# Sec_Controller_Sheet3.net
KiCad netlist of a schematic drawn in Altium Designer
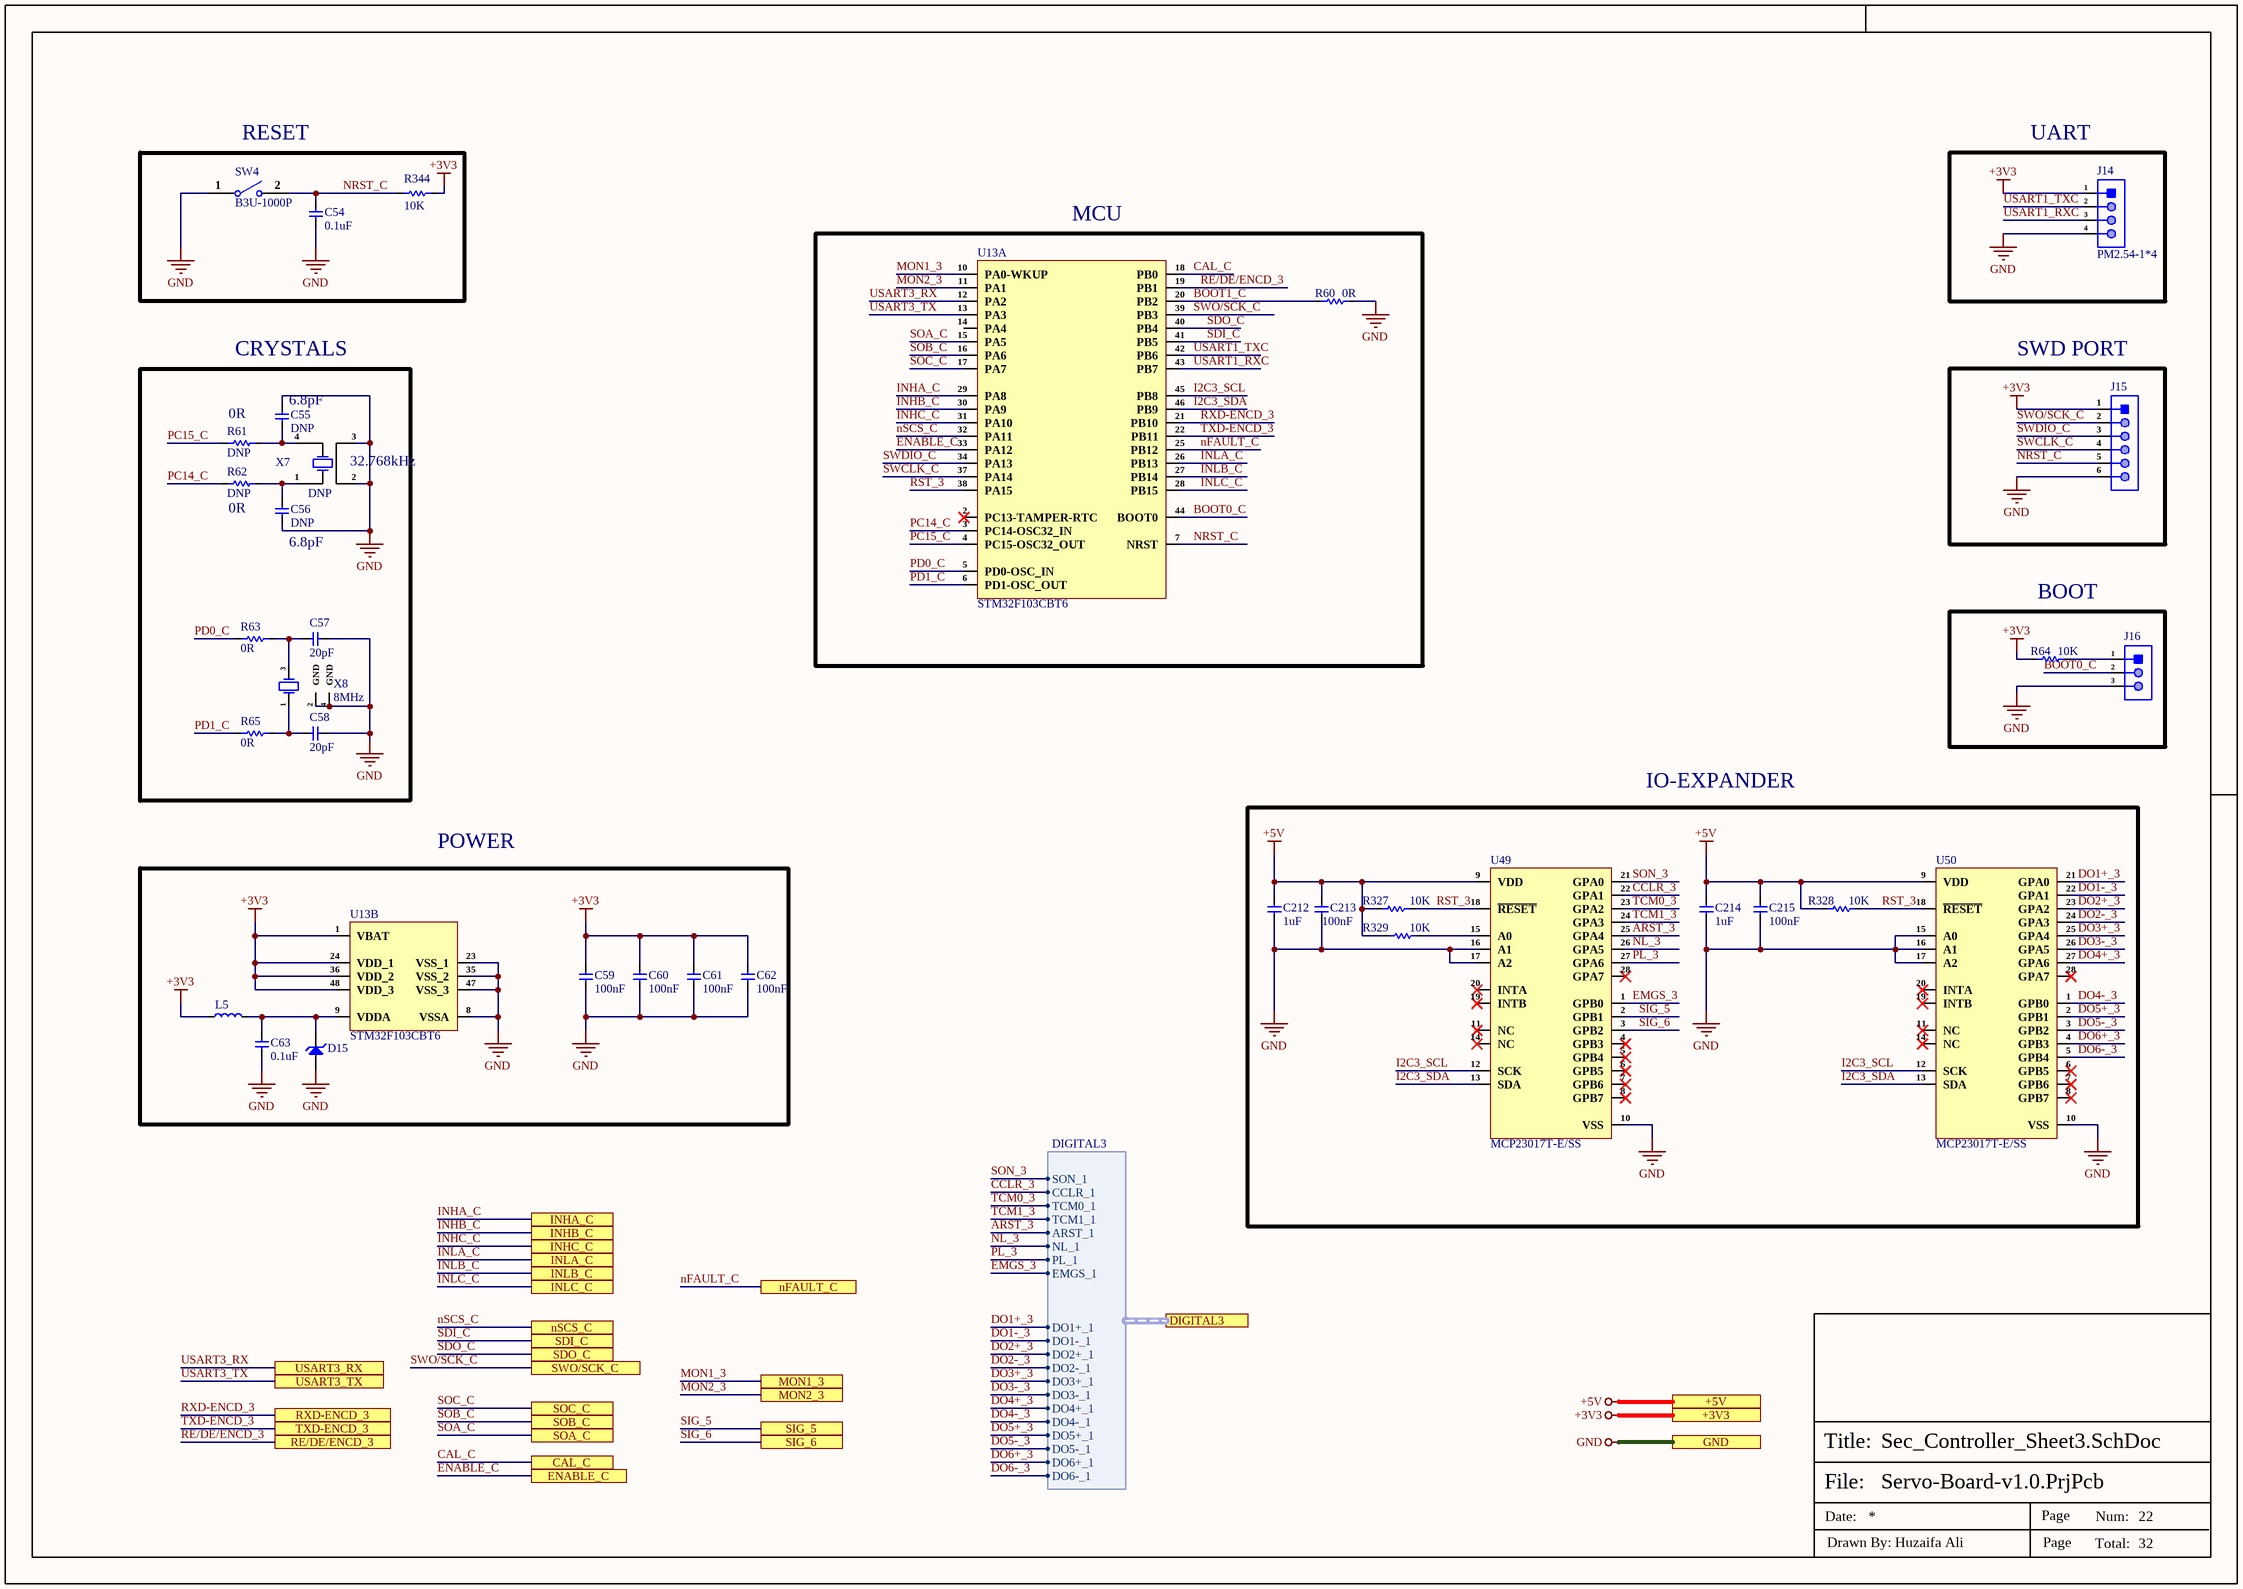
[diagram p0: Sec_Controller_Sheet3.SchDoc]

(export (version "E")
  (design (tool "Eeschema 10.0.6"))
  (components
    (comp (ref "C54")
      (value "0.1uF")
      (footprint "Cap-0402")
      (description "CAP CER 0.1UF 16V X7R 0402")
      (fields
        (field (name "MANUFACTURER") "Yageo")
        (field (name "MANUFACTURER PART NUMBER") "CC0402JRX7R7BB104")
      )
      (libsource (lib "eSpark Libraries") (part "CC0402JRX7R7BB104"))
    )
    (comp (ref "C55")
      (value "DNP")
      (footprint "Cap-0402")
      (description "CAP CER 6.8PF 50V C0G/NPO 0402")
      (fields
        (field (name "MANUFACTURER") "Yageo")
        (field (name "MANUFACTURER PART NUMBER") "CC0402CRNPO9BN6R8")
      )
      (libsource (lib "eSpark Libraries") (part "CC0402CRNPO9BN6R8"))
    )
    (comp (ref "C56")
      (value "DNP")
      (footprint "Cap-0402")
      (description "CAP CER 6.8PF 50V C0G/NPO 0402")
      (fields
        (field (name "MANUFACTURER") "Yageo")
        (field (name "MANUFACTURER PART NUMBER") "CC0402CRNPO9BN6R8")
      )
      (libsource (lib "eSpark Libraries") (part "CC0402CRNPO9BN6R8"))
    )
    (comp (ref "C57")
      (value "20pF")
      (footprint "Cap-0402")
      (description "CAP CER 20PF 50V C0G/NPO 0402")
      (fields (field (name "LCSC PART NUMBER") "C107000") (field (name "MANUFACTURER") "Yageo"))
      (libsource (lib "eSpark Libraries") (part "CC0402JRNPO9BN200"))
    )
    (comp (ref "C58")
      (value "20pF")
      (footprint "Cap-0402")
      (description "CAP CER 20PF 50V C0G/NPO 0402")
      (fields (field (name "LCSC PART NUMBER") "C107000") (field (name "MANUFACTURER") "Yageo"))
      (libsource (lib "eSpark Libraries") (part "CC0402JRNPO9BN200"))
    )
    (comp (ref "C59")
      (value "100nF")
      (footprint "cap-0402")
      (description "CAP CER 0.1UF 50V X7R 0402")
      (fields
        (field (name "MANUFACTURER") "TDK")
        (field (name "MANUFACTURER PART NUMBER") "C1005X7R1H104KT000F")
      )
      (libsource (lib "eSpark Libraries") (part "C1005X7R1H104KT000F"))
    )
    (comp (ref "C60")
      (value "100nF")
      (footprint "cap-0402")
      (description "CAP CER 0.1UF 50V X7R 0402")
      (fields
        (field (name "MANUFACTURER") "TDK")
        (field (name "MANUFACTURER PART NUMBER") "C1005X7R1H104KT000F")
      )
      (libsource (lib "eSpark Libraries") (part "C1005X7R1H104KT000F"))
    )
    (comp (ref "C61")
      (value "100nF")
      (footprint "cap-0402")
      (description "CAP CER 0.1UF 50V X7R 0402")
      (fields
        (field (name "MANUFACTURER") "TDK")
        (field (name "MANUFACTURER PART NUMBER") "C1005X7R1H104KT000F")
      )
      (libsource (lib "eSpark Libraries") (part "C1005X7R1H104KT000F"))
    )
    (comp (ref "C62")
      (value "100nF")
      (footprint "cap-0402")
      (description "CAP CER 0.1UF 50V X7R 0402")
      (fields
        (field (name "MANUFACTURER") "TDK")
        (field (name "MANUFACTURER PART NUMBER") "C1005X7R1H104KT000F")
      )
      (libsource (lib "eSpark Libraries") (part "C1005X7R1H104KT000F"))
    )
    (comp (ref "C63")
      (value "0.1uF")
      (footprint "Cap-0402")
      (description "CAP CER 0.1UF 16V X7R 0402")
      (fields
        (field (name "MANUFACTURER") "Yageo")
        (field (name "MANUFACTURER PART NUMBER") "CC0402JRX7R7BB104")
      )
      (libsource (lib "eSpark Libraries") (part "CC0402JRX7R7BB104"))
    )
    (comp (ref "C212")
      (value "1uF")
      (footprint "Cap-0402")
      (description "CAP CER 1UF 10V X5R 0402")
      (fields
        (field (name "MANUFACTURER") "Yageo")
        (field (name "MANUFACTURER PART NUMBER") "CC0402KRX5R6BB105")
      )
      (libsource (lib "eSpark Libraries") (part "CC0402KRX5R6BB105"))
    )
    (comp (ref "C213")
      (value "100nF")
      (footprint "cap-0402")
      (description "CAP CER 0.1UF 50V X7R 0402")
      (fields
        (field (name "MANUFACTURER") "TDK")
        (field (name "MANUFACTURER PART NUMBER") "C1005X7R1H104KT000F")
      )
      (libsource (lib "eSpark Libraries") (part "C1005X7R1H104KT000F"))
    )
    (comp (ref "C214")
      (value "1uF")
      (footprint "Cap-0402")
      (description "CAP CER 1UF 10V X5R 0402")
      (fields
        (field (name "MANUFACTURER") "Yageo")
        (field (name "MANUFACTURER PART NUMBER") "CC0402KRX5R6BB105")
      )
      (libsource (lib "eSpark Libraries") (part "CC0402KRX5R6BB105"))
    )
    (comp (ref "C215")
      (value "100nF")
      (footprint "cap-0402")
      (description "CAP CER 0.1UF 50V X7R 0402")
      (fields
        (field (name "MANUFACTURER") "TDK")
        (field (name "MANUFACTURER PART NUMBER") "C1005X7R1H104KT000F")
      )
      (libsource (lib "eSpark Libraries") (part "C1005X7R1H104KT000F"))
    )
    (comp (ref "D15")
      (value "AZ3003-01G")
      (footprint "SOD-123")
      (description "TVS SURGE PROTECTOR 1-CH 3.3V")
      (fields (field (name "MANUFACTURER") "Amazing"))
      (libsource (lib "eSpark Libraries") (part "AZ3003-01G"))
    )
    (comp (ref "J14")
      (value "PM2.54-1*4")
      (footprint "HDR1X4 Female")
      (fields (field (name "MANUFACTURER") "ZHOURI") (field (name "LCSC PART NUMBER") "C5116530"))
      (libsource (lib "eSpark Libraries") (part "PM2.54-1*4"))
    )
    (comp (ref "J15")
      (value "X6511WV-06H-C60D30")
      (footprint "HDR1X6_")
      (fields (field (name "MANUFACTURER") "XKB") (field (name "LCSC PART NUMBER") "C706878"))
      (libsource (lib "eSpark Libraries") (part "X6511WV-06H-C60D30"))
    )
    (comp (ref "J16")
      (value "68000-103HLF")
      (footprint "HDR1X3_")
      (description "CONN HEADER VERT 3POS 2.54MM")
      (fields (field (name "LCSC PART NUMBER") "C168677"))
      (libsource (lib "eSpark Libraries") (part "68000-103HLF"))
    )
    (comp (ref "L5")
      (value "BLM15AG601SN1D")
      (footprint "IND-0402")
      (description "FERRITE BEAD 600 OHM 0402 1LN")
      (fields (field (name "MANUFACTURER") "Murata") (field (name "TOLERANCE") "25%"))
      (libsource (lib "eSpark Libraries") (part "BLM15AG601SN1D"))
    )
    (comp (ref "R60")
      (value "0R")
      (footprint "Res-0402")
      (description "RES 0 OHM JUMPER 1/16W 0402")
      (fields
        (field (name "MANUFACTURER") "Yageo")
        (field (name "MANUFACTURER PART NUMBER") "RC0402FR-070RL")
      )
      (libsource (lib "eSpark Libraries") (part "RC0402FR-070RL"))
    )
    (comp (ref "R61")
      (value "DNP")
      (footprint "Res-0603")
      (description "RES 0 OHM JUMPER 1/10W 0603")
      (fields
        (field (name "MANUFACTURER") "Yageo")
        (field (name "MANUFACTURER PART NUMBER") "RC0603JR-070RL")
      )
      (libsource (lib "eSpark Libraries") (part "RC0603JR-070RL"))
    )
    (comp (ref "R62")
      (value "DNP")
      (footprint "Res-0603")
      (description "RES 0 OHM JUMPER 1/10W 0603")
      (fields
        (field (name "MANUFACTURER") "Yageo")
        (field (name "MANUFACTURER PART NUMBER") "RC0603JR-070RL")
      )
      (libsource (lib "eSpark Libraries") (part "RC0603JR-070RL"))
    )
    (comp (ref "R63")
      (value "0R")
      (footprint "Res-0603")
      (description "RES 0 OHM JUMPER 1/10W 0603")
      (fields
        (field (name "MANUFACTURER") "Yageo")
        (field (name "MANUFACTURER PART NUMBER") "RC0603JR-070RL")
      )
      (libsource (lib "eSpark Libraries") (part "RC0603JR-070RL"))
    )
    (comp (ref "R64")
      (value "10K")
      (footprint "Res-0402")
      (description "RES 10K OHM 1% 1/16W 0402")
      (fields
        (field (name "MANUFACTURER") "Yageo")
        (field (name "MANUFACTURER PART NUMBER") "RC0402FR-0710KL")
      )
      (libsource (lib "eSpark Libraries") (part "RC0402FR-0710KL"))
    )
    (comp (ref "R65")
      (value "0R")
      (footprint "Res-0603")
      (description "RES 0 OHM JUMPER 1/10W 0603")
      (fields
        (field (name "MANUFACTURER") "Yageo")
        (field (name "MANUFACTURER PART NUMBER") "RC0603JR-070RL")
      )
      (libsource (lib "eSpark Libraries") (part "RC0603JR-070RL"))
    )
    (comp (ref "R327")
      (value "10K")
      (footprint "Res-0402")
      (description "RES 10K OHM 1% 1/16W 0402")
      (fields
        (field (name "MANUFACTURER") "Yageo")
        (field (name "MANUFACTURER PART NUMBER") "RC0402FR-0710KL")
      )
      (libsource (lib "eSpark Libraries") (part "RC0402FR-0710KL"))
    )
    (comp (ref "R328")
      (value "10K")
      (footprint "Res-0402")
      (description "RES 10K OHM 1% 1/16W 0402")
      (fields
        (field (name "MANUFACTURER") "Yageo")
        (field (name "MANUFACTURER PART NUMBER") "RC0402FR-0710KL")
      )
      (libsource (lib "eSpark Libraries") (part "RC0402FR-0710KL"))
    )
    (comp (ref "R329")
      (value "10K")
      (footprint "Res-0402")
      (description "RES 10K OHM 1% 1/16W 0402")
      (fields
        (field (name "MANUFACTURER") "Yageo")
        (field (name "MANUFACTURER PART NUMBER") "RC0402FR-0710KL")
      )
      (libsource (lib "eSpark Libraries") (part "RC0402FR-0710KL"))
    )
    (comp (ref "R344")
      (value "10K")
      (footprint "Res-0402")
      (description "RES 10K OHM 1% 1/16W 0402")
      (fields
        (field (name "MANUFACTURER") "Yageo")
        (field (name "MANUFACTURER PART NUMBER") "RC0402FR-0710KL")
      )
      (libsource (lib "eSpark Libraries") (part "RC0402FR-0710KL"))
    )
    (comp (ref "SW4")
      (value "B3U-1000P")
      (footprint "B3U-1000P")
      (description "SWITCH TACTILE SPST-NO 0.05A 12V")
      (fields (field (name "MANUFACTURER") "Omron") (field (name "LCSC PART NUMBER") "C231329"))
      (libsource (lib "eSpark Libraries") (part "B3U-1000P"))
    )
    (comp (ref "U13")
      (value "STM32F103CBT6")
      (footprint "48-LQFP (7x7)_")
      (description "IC MCU 32BIT 128KB FLASH 48LQFP")
      (fields (field (name "MANUFACTURER") "STMicroelectronics") (field (name "LCSC PART NUMBER") "C8304"))
      (libsource (lib "eSpark Libraries") (part "STM32F103CBT6"))
    )
    (comp (ref "U49")
      (value "MCP23017T-E/SS")
      (footprint "SSOP-28-208mil")
      (description "IC XPNDR 1.7MHZ I2C 28SSOP")
      (fields (field (name "MANUFACTURER") "Microchip") (field (name "LCSC PART NUMBER") "C558584"))
      (libsource (lib "eSpark Libraries") (part "MCP23017T-E/SS"))
    )
    (comp (ref "U50")
      (value "MCP23017T-E/SS")
      (footprint "SSOP-28-208mil")
      (description "IC XPNDR 1.7MHZ I2C 28SSOP")
      (fields (field (name "MANUFACTURER") "Microchip") (field (name "LCSC PART NUMBER") "C558584"))
      (libsource (lib "eSpark Libraries") (part "MCP23017T-E/SS"))
    )
    (comp (ref "X7")
      (value "DNP")
      (footprint "MC-306")
      (description "32.768kHz 12.5pF ±20ppm MC-306 Crystals ROHS")
      (fields
        (field (name "MANUFACTURER") "Seiko Epson")
        (field (name "MANUFACTURER PART NUMBER") "MC-306 32.7680K-A0:ROHS")
      )
      (libsource (lib "eSpark Libraries") (part "MC-306 32.7680K-A0{colon}ROHS"))
    )
    (comp (ref "X8")
      (value "8MHz")
      (footprint "5TJ480000XYLBC_")
      (description "8MHz 18pF ±10ppm SMD5032-4P Crystals ROHS")
      (fields (field (name "MANUFACTURER") "JYJE") (field (name "MANUFACTURER PART NUMBER") "5TJ480000XYLBC"))
      (libsource (lib "eSpark Libraries") (part "5TJ480000XYLBC"))
    )
  )
  (nets
    (net (code "2") (name "+3V3") (class "Default")
      (node (ref "C59") (pin "2") (pinfunction "2_2") (pintype "passive"))
      (node (ref "C60") (pin "2") (pinfunction "2_2") (pintype "passive"))
      (node (ref "C61") (pin "2") (pinfunction "2_2") (pintype "passive"))
      (node (ref "C62") (pin "2") (pinfunction "2_2") (pintype "passive"))
      (node (ref "J14") (pin "1") (pinfunction "1_1") (pintype "passive"))
      (node (ref "J15") (pin "1") (pinfunction "1_1") (pintype "passive"))
      (node (ref "L5") (pin "1") (pinfunction "1_1") (pintype "passive"))
      (node (ref "R344") (pin "2") (pinfunction "2_2") (pintype "passive"))
      (node (ref "R64") (pin "2") (pinfunction "2_2") (pintype "passive"))
      (node (ref "U13") (pin "1") (pinfunction "VBAT_1") (pintype "power_in"))
      (node (ref "U13") (pin "24") (pinfunction "VDD_1_24") (pintype "power_in"))
      (node (ref "U13") (pin "36") (pinfunction "VDD_2_36") (pintype "power_in"))
      (node (ref "U13") (pin "48") (pinfunction "VDD_3_48") (pintype "power_in"))
    )
    (net (code "3") (name "+5V") (class "Default")
      (node (ref "C212") (pin "2") (pinfunction "2_2") (pintype "passive"))
      (node (ref "C213") (pin "2") (pinfunction "2_2") (pintype "passive"))
      (node (ref "C214") (pin "2") (pinfunction "2_2") (pintype "passive"))
      (node (ref "C215") (pin "2") (pinfunction "2_2") (pintype "passive"))
      (node (ref "R327") (pin "2") (pinfunction "2_2") (pintype "passive"))
      (node (ref "R328") (pin "2") (pinfunction "2_2") (pintype "passive"))
      (node (ref "R329") (pin "2") (pinfunction "2_2") (pintype "passive"))
      (node (ref "U49") (pin "9") (pinfunction "VDD_9") (pintype "passive"))
      (node (ref "U50") (pin "9") (pinfunction "VDD_9") (pintype "passive"))
    )
    (net (code "4") (name "/ARST_3") (class "Default")
      (node (ref "U49") (pin "25") (pinfunction "GPA4_25") (pintype "passive"))
    )
    (net (code "5") (name "/BOOT0_C") (class "Default")
      (node (ref "J16") (pin "2") (pinfunction "2_2") (pintype "passive"))
      (node (ref "U13") (pin "44") (pinfunction "BOOT0_44") (pintype "passive"))
    )
    (net (code "6") (name "/BOOT1_C") (class "Default")
      (node (ref "R60") (pin "1") (pinfunction "1_1") (pintype "passive"))
      (node (ref "U13") (pin "20") (pinfunction "PB2_20") (pintype "passive"))
    )
    (net (code "7") (name "/CAL_C") (class "Default")
      (node (ref "U13") (pin "18") (pinfunction "PB0_18") (pintype "passive"))
    )
    (net (code "8") (name "/CCLR_3") (class "Default")
      (node (ref "U49") (pin "22") (pinfunction "GPA1_22") (pintype "passive"))
    )
    (net (code "9") (name "/DO1+_3") (class "Default")
      (node (ref "U50") (pin "21") (pinfunction "GPA0_21") (pintype "passive"))
    )
    (net (code "10") (name "/DO1-_3") (class "Default")
      (node (ref "U50") (pin "22") (pinfunction "GPA1_22") (pintype "passive"))
    )
    (net (code "11") (name "/DO2+_3") (class "Default")
      (node (ref "U50") (pin "23") (pinfunction "GPA2_23") (pintype "passive"))
    )
    (net (code "12") (name "/DO2-_3") (class "Default")
      (node (ref "U50") (pin "24") (pinfunction "GPA3_24") (pintype "passive"))
    )
    (net (code "13") (name "/DO3+_3") (class "Default")
      (node (ref "U50") (pin "25") (pinfunction "GPA4_25") (pintype "passive"))
    )
    (net (code "14") (name "/DO3-_3") (class "Default")
      (node (ref "U50") (pin "26") (pinfunction "GPA5_26") (pintype "passive"))
    )
    (net (code "15") (name "/DO4+_3") (class "Default")
      (node (ref "U50") (pin "27") (pinfunction "GPA6_27") (pintype "passive"))
    )
    (net (code "16") (name "/DO4-_3") (class "Default")
      (node (ref "U50") (pin "1") (pinfunction "GPB0_1") (pintype "passive"))
    )
    (net (code "17") (name "/DO5+_3") (class "Default")
      (node (ref "U50") (pin "2") (pinfunction "GPB1_2") (pintype "passive"))
    )
    (net (code "18") (name "/DO5-_3") (class "Default")
      (node (ref "U50") (pin "3") (pinfunction "GPB2_3") (pintype "passive"))
    )
    (net (code "19") (name "/DO6+_3") (class "Default")
      (node (ref "U50") (pin "4") (pinfunction "GPB3_4") (pintype "passive"))
    )
    (net (code "20") (name "/DO6-_3") (class "Default")
      (node (ref "U50") (pin "5") (pinfunction "GPB4_5") (pintype "passive"))
    )
    (net (code "21") (name "/EMGS_3") (class "Default")
      (node (ref "U49") (pin "1") (pinfunction "GPB0_1") (pintype "passive"))
    )
    (net (code "22") (name "/ENABLE_C") (class "Default")
      (node (ref "U13") (pin "33") (pinfunction "PA12_33") (pintype "passive"))
    )
    (net (code "23") (name "/I2C3_SCL") (class "Default")
      (node (ref "U13") (pin "45") (pinfunction "PB8_45") (pintype "passive"))
      (node (ref "U49") (pin "12") (pinfunction "SCK_12") (pintype "passive"))
      (node (ref "U50") (pin "12") (pinfunction "SCK_12") (pintype "passive"))
    )
    (net (code "24") (name "/I2C3_SDA") (class "Default")
      (node (ref "U13") (pin "46") (pinfunction "PB9_46") (pintype "passive"))
      (node (ref "U49") (pin "13") (pinfunction "SDA_13") (pintype "passive"))
      (node (ref "U50") (pin "13") (pinfunction "SDA_13") (pintype "passive"))
    )
    (net (code "25") (name "/INHA_C") (class "Default")
      (node (ref "U13") (pin "29") (pinfunction "PA8_29") (pintype "passive"))
    )
    (net (code "26") (name "/INHB_C") (class "Default")
      (node (ref "U13") (pin "30") (pinfunction "PA9_30") (pintype "passive"))
    )
    (net (code "27") (name "/INHC_C") (class "Default")
      (node (ref "U13") (pin "31") (pinfunction "PA10_31") (pintype "passive"))
    )
    (net (code "28") (name "/INLA_C") (class "Default")
      (node (ref "U13") (pin "26") (pinfunction "PB13_26") (pintype "passive"))
    )
    (net (code "29") (name "/INLB_C") (class "Default")
      (node (ref "U13") (pin "27") (pinfunction "PB14_27") (pintype "passive"))
    )
    (net (code "30") (name "/INLC_C") (class "Default")
      (node (ref "U13") (pin "28") (pinfunction "PB15_28") (pintype "passive"))
    )
    (net (code "31") (name "/MON1_3") (class "Default")
      (node (ref "U13") (pin "10") (pinfunction "PA0-WKUP_10") (pintype "passive"))
    )
    (net (code "32") (name "/MON2_3") (class "Default")
      (node (ref "U13") (pin "11") (pinfunction "PA1_11") (pintype "passive"))
    )
    (net (code "33") (name "/NL_3") (class "Default")
      (node (ref "U49") (pin "26") (pinfunction "GPA5_26") (pintype "passive"))
    )
    (net (code "34") (name "/NRST_C") (class "Default")
      (node (ref "C54") (pin "2") (pinfunction "2_2") (pintype "passive"))
      (node (ref "J15") (pin "5") (pinfunction "5_5") (pintype "passive"))
      (node (ref "R344") (pin "1") (pinfunction "1_1") (pintype "passive"))
      (node (ref "SW4") (pin "2") (pinfunction "2_2") (pintype "passive"))
      (node (ref "U13") (pin "7") (pinfunction "NRST_7") (pintype "passive"))
    )
    (net (code "35") (name "/PC14_C") (class "Default")
      (node (ref "R62") (pin "2") (pinfunction "2_2") (pintype "passive"))
      (node (ref "U13") (pin "3") (pinfunction "PC14-OSC32_IN_3") (pintype "passive"))
    )
    (net (code "36") (name "/PC15_C") (class "Default")
      (node (ref "R61") (pin "2") (pinfunction "2_2") (pintype "passive"))
      (node (ref "U13") (pin "4") (pinfunction "PC15-OSC32_OUT_4") (pintype "passive"))
    )
    (net (code "37") (name "/PD0_C") (class "Default")
      (node (ref "R63") (pin "2") (pinfunction "2_2") (pintype "passive"))
      (node (ref "U13") (pin "5") (pinfunction "PD0-OSC_IN_5") (pintype "passive"))
    )
    (net (code "38") (name "/PD1_C") (class "Default")
      (node (ref "R65") (pin "2") (pinfunction "2_2") (pintype "passive"))
      (node (ref "U13") (pin "6") (pinfunction "PD1-OSC_OUT_6") (pintype "passive"))
    )
    (net (code "39") (name "/PL_3") (class "Default")
      (node (ref "U49") (pin "27") (pinfunction "GPA6_27") (pintype "passive"))
    )
    (net (code "40") (name "/RE{slash}DE{slash}ENCD_3") (class "Default")
      (node (ref "U13") (pin "19") (pinfunction "PB1_19") (pintype "passive"))
    )
    (net (code "41") (name "/RST_3") (class "Default")
      (node (ref "R327") (pin "1") (pinfunction "1_1") (pintype "passive"))
      (node (ref "R328") (pin "1") (pinfunction "1_1") (pintype "passive"))
      (node (ref "U13") (pin "38") (pinfunction "PA15_38") (pintype "passive"))
      (node (ref "U49") (pin "18") (pinfunction "~{RESET}_18") (pintype "passive"))
      (node (ref "U50") (pin "18") (pinfunction "~{RESET}_18") (pintype "passive"))
    )
    (net (code "42") (name "/RXD-ENCD_3") (class "Default")
      (node (ref "U13") (pin "21") (pinfunction "PB10_21") (pintype "passive"))
    )
    (net (code "43") (name "/SDI_C") (class "Default")
      (node (ref "U13") (pin "41") (pinfunction "PB5_41") (pintype "passive"))
    )
    (net (code "44") (name "/SDO_C") (class "Default")
      (node (ref "U13") (pin "40") (pinfunction "PB4_40") (pintype "passive"))
    )
    (net (code "45") (name "/SIG_5") (class "Default")
      (node (ref "U49") (pin "2") (pinfunction "GPB1_2") (pintype "passive"))
    )
    (net (code "46") (name "/SIG_6") (class "Default")
      (node (ref "U49") (pin "3") (pinfunction "GPB2_3") (pintype "passive"))
    )
    (net (code "47") (name "/SOA_C") (class "Default")
      (node (ref "U13") (pin "15") (pinfunction "PA5_15") (pintype "passive"))
    )
    (net (code "48") (name "/SOB_C") (class "Default")
      (node (ref "U13") (pin "16") (pinfunction "PA6_16") (pintype "passive"))
    )
    (net (code "49") (name "/SOC_C") (class "Default")
      (node (ref "U13") (pin "17") (pinfunction "PA7_17") (pintype "passive"))
    )
    (net (code "50") (name "/SON_3") (class "Default")
      (node (ref "U49") (pin "21") (pinfunction "GPA0_21") (pintype "passive"))
    )
    (net (code "51") (name "/SWCLK_C") (class "Default")
      (node (ref "J15") (pin "4") (pinfunction "4_4") (pintype "passive"))
      (node (ref "U13") (pin "37") (pinfunction "PA14_37") (pintype "passive"))
    )
    (net (code "52") (name "/SWDIO_C") (class "Default")
      (node (ref "J15") (pin "3") (pinfunction "3_3") (pintype "passive"))
      (node (ref "U13") (pin "34") (pinfunction "PA13_34") (pintype "passive"))
    )
    (net (code "53") (name "/SWO{slash}SCK_C") (class "Default")
      (node (ref "J15") (pin "2") (pinfunction "2_2") (pintype "passive"))
      (node (ref "U13") (pin "39") (pinfunction "PB3_39") (pintype "passive"))
    )
    (net (code "54") (name "/TCM0_3") (class "Default")
      (node (ref "U49") (pin "23") (pinfunction "GPA2_23") (pintype "passive"))
    )
    (net (code "55") (name "/TCM1_3") (class "Default")
      (node (ref "U49") (pin "24") (pinfunction "GPA3_24") (pintype "passive"))
    )
    (net (code "56") (name "/TXD-ENCD_3") (class "Default")
      (node (ref "U13") (pin "22") (pinfunction "PB11_22") (pintype "passive"))
    )
    (net (code "57") (name "/USART1_RXC") (class "Default")
      (node (ref "J14") (pin "3") (pinfunction "3_3") (pintype "passive"))
      (node (ref "U13") (pin "43") (pinfunction "PB7_43") (pintype "passive"))
    )
    (net (code "58") (name "/USART1_TXC") (class "Default")
      (node (ref "J14") (pin "2") (pinfunction "2_2") (pintype "passive"))
      (node (ref "U13") (pin "42") (pinfunction "PB6_42") (pintype "passive"))
    )
    (net (code "59") (name "/USART3_RX") (class "Default")
      (node (ref "U13") (pin "12") (pinfunction "PA2_12") (pintype "passive"))
    )
    (net (code "60") (name "/USART3_TX") (class "Default")
      (node (ref "U13") (pin "13") (pinfunction "PA3_13") (pintype "passive"))
    )
    (net (code "61") (name "/nFAULT_C") (class "Default")
      (node (ref "U13") (pin "25") (pinfunction "PB12_25") (pintype "passive"))
    )
    (net (code "62") (name "/nSCS_C") (class "Default")
      (node (ref "U13") (pin "32") (pinfunction "PA11_32") (pintype "passive"))
    )
    (net (code "64") (name "GND") (class "Default")
      (node (ref "C212") (pin "1") (pinfunction "1_1") (pintype "passive"))
      (node (ref "C213") (pin "1") (pinfunction "1_1") (pintype "passive"))
      (node (ref "C214") (pin "1") (pinfunction "1_1") (pintype "passive"))
      (node (ref "C215") (pin "1") (pinfunction "1_1") (pintype "passive"))
      (node (ref "C54") (pin "1") (pinfunction "1_1") (pintype "passive"))
      (node (ref "C55") (pin "2") (pinfunction "2_2") (pintype "passive"))
      (node (ref "C56") (pin "1") (pinfunction "1_1") (pintype "passive"))
      (node (ref "C57") (pin "2") (pinfunction "2_2") (pintype "passive"))
      (node (ref "C58") (pin "2") (pinfunction "2_2") (pintype "passive"))
      (node (ref "C59") (pin "1") (pinfunction "1_1") (pintype "passive"))
      (node (ref "C60") (pin "1") (pinfunction "1_1") (pintype "passive"))
      (node (ref "C61") (pin "1") (pinfunction "1_1") (pintype "passive"))
      (node (ref "C62") (pin "1") (pinfunction "1_1") (pintype "passive"))
      (node (ref "C63") (pin "1") (pinfunction "1_1") (pintype "passive"))
      (node (ref "D15") (pin "1") (pinfunction "A_1") (pintype "passive"))
      (node (ref "J14") (pin "4") (pinfunction "4_4") (pintype "passive"))
      (node (ref "J15") (pin "6") (pinfunction "6_6") (pintype "passive"))
      (node (ref "J16") (pin "3") (pinfunction "3_3") (pintype "passive"))
      (node (ref "R60") (pin "2") (pinfunction "2_2") (pintype "passive"))
      (node (ref "SW4") (pin "1") (pinfunction "1_1") (pintype "passive"))
      (node (ref "U13") (pin "23") (pinfunction "VSS_1_23") (pintype "power_in"))
      (node (ref "U13") (pin "35") (pinfunction "VSS_2_35") (pintype "power_in"))
      (node (ref "U13") (pin "47") (pinfunction "VSS_3_47") (pintype "power_in"))
      (node (ref "U13") (pin "8") (pinfunction "VSSA_8") (pintype "power_in"))
      (node (ref "U49") (pin "10") (pinfunction "VSS_10") (pintype "passive"))
      (node (ref "U49") (pin "16") (pinfunction "A1_16") (pintype "passive"))
      (node (ref "U49") (pin "17") (pinfunction "A2_17") (pintype "passive"))
      (node (ref "U50") (pin "10") (pinfunction "VSS_10") (pintype "passive"))
      (node (ref "U50") (pin "15") (pinfunction "A0_15") (pintype "passive"))
      (node (ref "U50") (pin "16") (pinfunction "A1_16") (pintype "passive"))
      (node (ref "U50") (pin "17") (pinfunction "A2_17") (pintype "passive"))
      (node (ref "X7") (pin "2") (pinfunction "2_2") (pintype "passive"))
      (node (ref "X7") (pin "3") (pinfunction "3_3") (pintype "passive"))
      (node (ref "X8") (pin "2") (pinfunction "GND_2") (pintype "passive"))
      (node (ref "X8") (pin "4") (pinfunction "GND_4") (pintype "passive"))
    )
    (net (code "65") (name "Net-(D15-K)") (class "Default")
      (node (ref "C63") (pin "2") (pinfunction "2_2") (pintype "passive"))
      (node (ref "D15") (pin "2") (pinfunction "K_2") (pintype "passive"))
      (node (ref "L5") (pin "2") (pinfunction "2_2") (pintype "passive"))
      (node (ref "U13") (pin "9") (pinfunction "VDDA_9") (pintype "power_in"))
    )
    (net (code "66") (name "Net-(J16-Pad1)") (class "Default")
      (node (ref "J16") (pin "1") (pinfunction "1_1") (pintype "passive"))
      (node (ref "R64") (pin "1") (pinfunction "1_1") (pintype "passive"))
    )
    (net (code "67") (name "Net-(U49-A0)") (class "Default")
      (node (ref "R329") (pin "1") (pinfunction "1_1") (pintype "passive"))
      (node (ref "U49") (pin "15") (pinfunction "A0_15") (pintype "passive"))
    )
    (net (code "68") (name "Net-(X7-OSC1)") (class "Default")
      (node (ref "C56") (pin "2") (pinfunction "2_2") (pintype "passive"))
      (node (ref "R62") (pin "1") (pinfunction "1_1") (pintype "passive"))
      (node (ref "X7") (pin "1") (pinfunction "OSC1_1") (pintype "passive"))
    )
    (net (code "69") (name "Net-(X7-OSC2)") (class "Default")
      (node (ref "C55") (pin "1") (pinfunction "1_1") (pintype "passive"))
      (node (ref "R61") (pin "1") (pinfunction "1_1") (pintype "passive"))
      (node (ref "X7") (pin "4") (pinfunction "OSC2_4") (pintype "passive"))
    )
    (net (code "70") (name "Net-(X8-OSC1)") (class "Default")
      (node (ref "C58") (pin "1") (pinfunction "1_1") (pintype "passive"))
      (node (ref "R65") (pin "1") (pinfunction "1_1") (pintype "passive"))
      (node (ref "X8") (pin "1") (pinfunction "OSC1_1") (pintype "passive"))
    )
    (net (code "71") (name "Net-(X8-OSC2)") (class "Default")
      (node (ref "C57") (pin "1") (pinfunction "1_1") (pintype "passive"))
      (node (ref "R63") (pin "1") (pinfunction "1_1") (pintype "passive"))
      (node (ref "X8") (pin "3") (pinfunction "OSC2_3") (pintype "passive"))
    )
    (net (code "72") (name "unconnected-(U13A-PA4-Pad14)") (class "Default")
      (node (ref "U13") (pin "14") (pinfunction "PA4_14") (pintype "passive"))
    )
    (net (code "73") (name "unconnected-(U13A-PC13-TAMPER-RTC-Pad2)") (class "Default")
      (node (ref "U13") (pin "2") (pinfunction "PC13-TAMPER-RTC_2") (pintype "passive+no_connect"))
    )
    (net (code "74") (name "unconnected-(U49-GPA7-Pad28)") (class "Default")
      (node (ref "U49") (pin "28") (pinfunction "GPA7_28") (pintype "passive+no_connect"))
    )
    (net (code "75") (name "unconnected-(U49-GPB3-Pad4)") (class "Default")
      (node (ref "U49") (pin "4") (pinfunction "GPB3_4") (pintype "passive+no_connect"))
    )
    (net (code "76") (name "unconnected-(U49-GPB4-Pad5)") (class "Default")
      (node (ref "U49") (pin "5") (pinfunction "GPB4_5") (pintype "passive+no_connect"))
    )
    (net (code "77") (name "unconnected-(U49-GPB5-Pad6)") (class "Default")
      (node (ref "U49") (pin "6") (pinfunction "GPB5_6") (pintype "passive+no_connect"))
    )
    (net (code "78") (name "unconnected-(U49-GPB6-Pad7)") (class "Default")
      (node (ref "U49") (pin "7") (pinfunction "GPB6_7") (pintype "passive+no_connect"))
    )
    (net (code "79") (name "unconnected-(U49-GPB7-Pad8)") (class "Default")
      (node (ref "U49") (pin "8") (pinfunction "GPB7_8") (pintype "passive+no_connect"))
    )
    (net (code "80") (name "unconnected-(U49-INTA-Pad20)") (class "Default")
      (node (ref "U49") (pin "20") (pinfunction "INTA_20") (pintype "passive+no_connect"))
    )
    (net (code "81") (name "unconnected-(U49-INTB-Pad19)") (class "Default")
      (node (ref "U49") (pin "19") (pinfunction "INTB_19") (pintype "passive+no_connect"))
    )
    (net (code "82") (name "unconnected-(U49-NC-Pad11)") (class "Default")
      (node (ref "U49") (pin "11") (pinfunction "NC_11") (pintype "passive+no_connect"))
    )
    (net (code "83") (name "unconnected-(U49-NC-Pad14)") (class "Default")
      (node (ref "U49") (pin "14") (pinfunction "NC_14") (pintype "passive+no_connect"))
    )
    (net (code "84") (name "unconnected-(U50-GPA7-Pad28)") (class "Default")
      (node (ref "U50") (pin "28") (pinfunction "GPA7_28") (pintype "passive+no_connect"))
    )
    (net (code "85") (name "unconnected-(U50-GPB5-Pad6)") (class "Default")
      (node (ref "U50") (pin "6") (pinfunction "GPB5_6") (pintype "passive+no_connect"))
    )
    (net (code "86") (name "unconnected-(U50-GPB6-Pad7)") (class "Default")
      (node (ref "U50") (pin "7") (pinfunction "GPB6_7") (pintype "passive+no_connect"))
    )
    (net (code "87") (name "unconnected-(U50-GPB7-Pad8)") (class "Default")
      (node (ref "U50") (pin "8") (pinfunction "GPB7_8") (pintype "passive+no_connect"))
    )
    (net (code "88") (name "unconnected-(U50-INTA-Pad20)") (class "Default")
      (node (ref "U50") (pin "20") (pinfunction "INTA_20") (pintype "passive+no_connect"))
    )
    (net (code "89") (name "unconnected-(U50-INTB-Pad19)") (class "Default")
      (node (ref "U50") (pin "19") (pinfunction "INTB_19") (pintype "passive+no_connect"))
    )
    (net (code "90") (name "unconnected-(U50-NC-Pad11)") (class "Default")
      (node (ref "U50") (pin "11") (pinfunction "NC_11") (pintype "passive+no_connect"))
    )
    (net (code "91") (name "unconnected-(U50-NC-Pad14)") (class "Default")
      (node (ref "U50") (pin "14") (pinfunction "NC_14") (pintype "passive+no_connect"))
    )
  )
)
